# hodiny.net
KiCad netlist of a schematic drawn in EAGLE
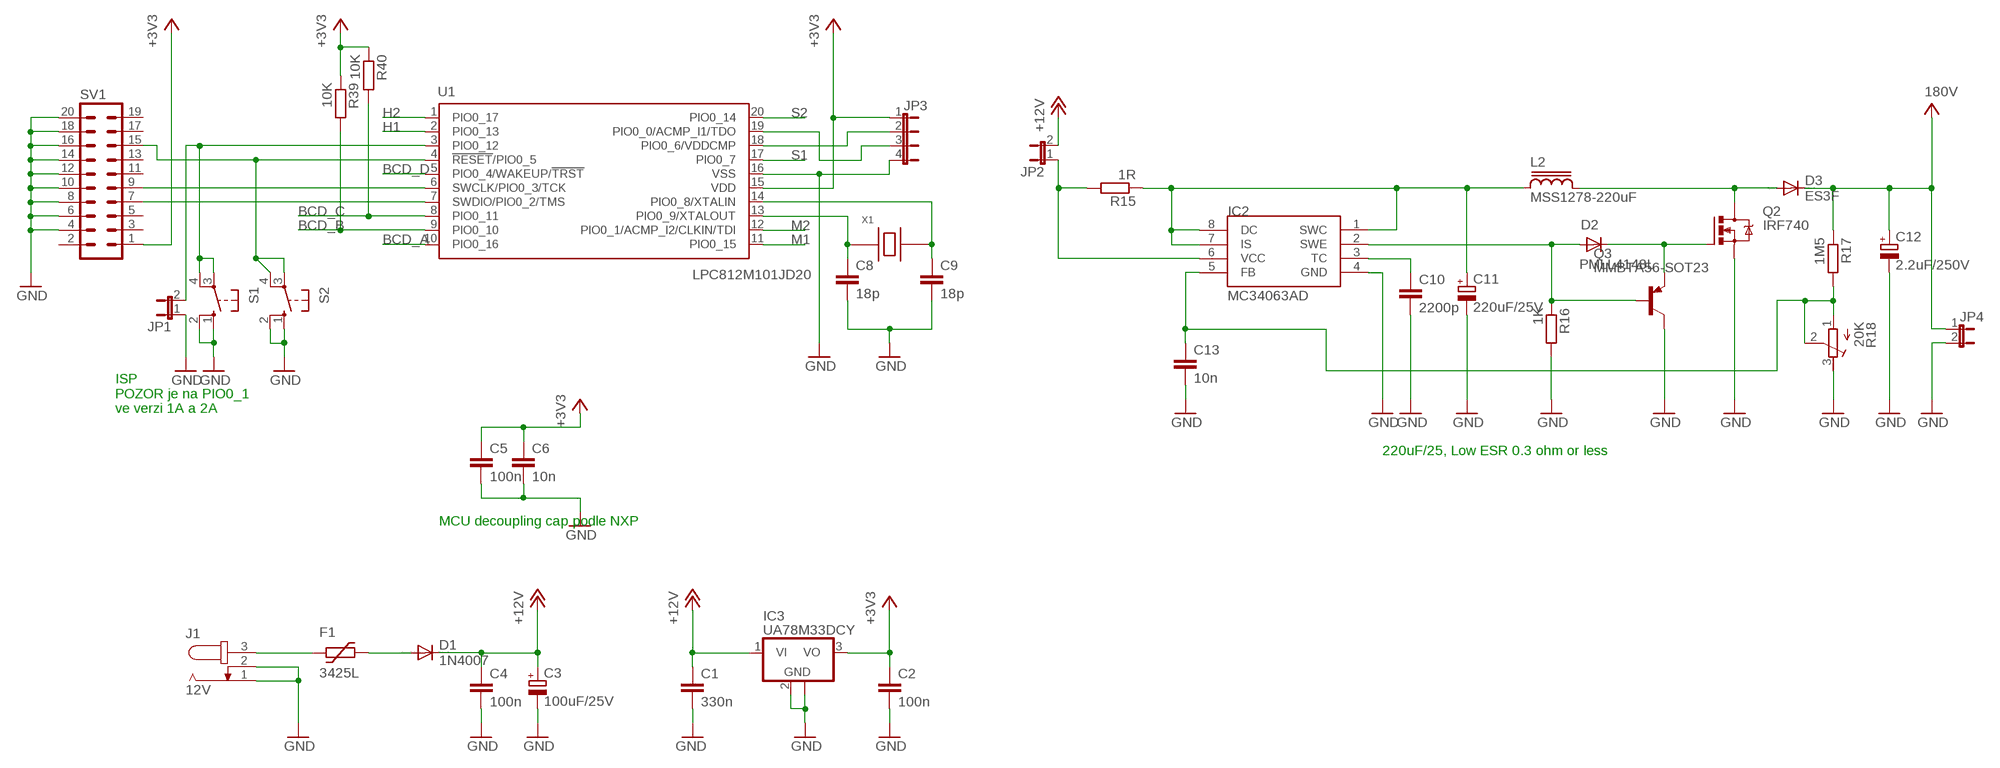
[diagram p0: schematic, sheet 1]
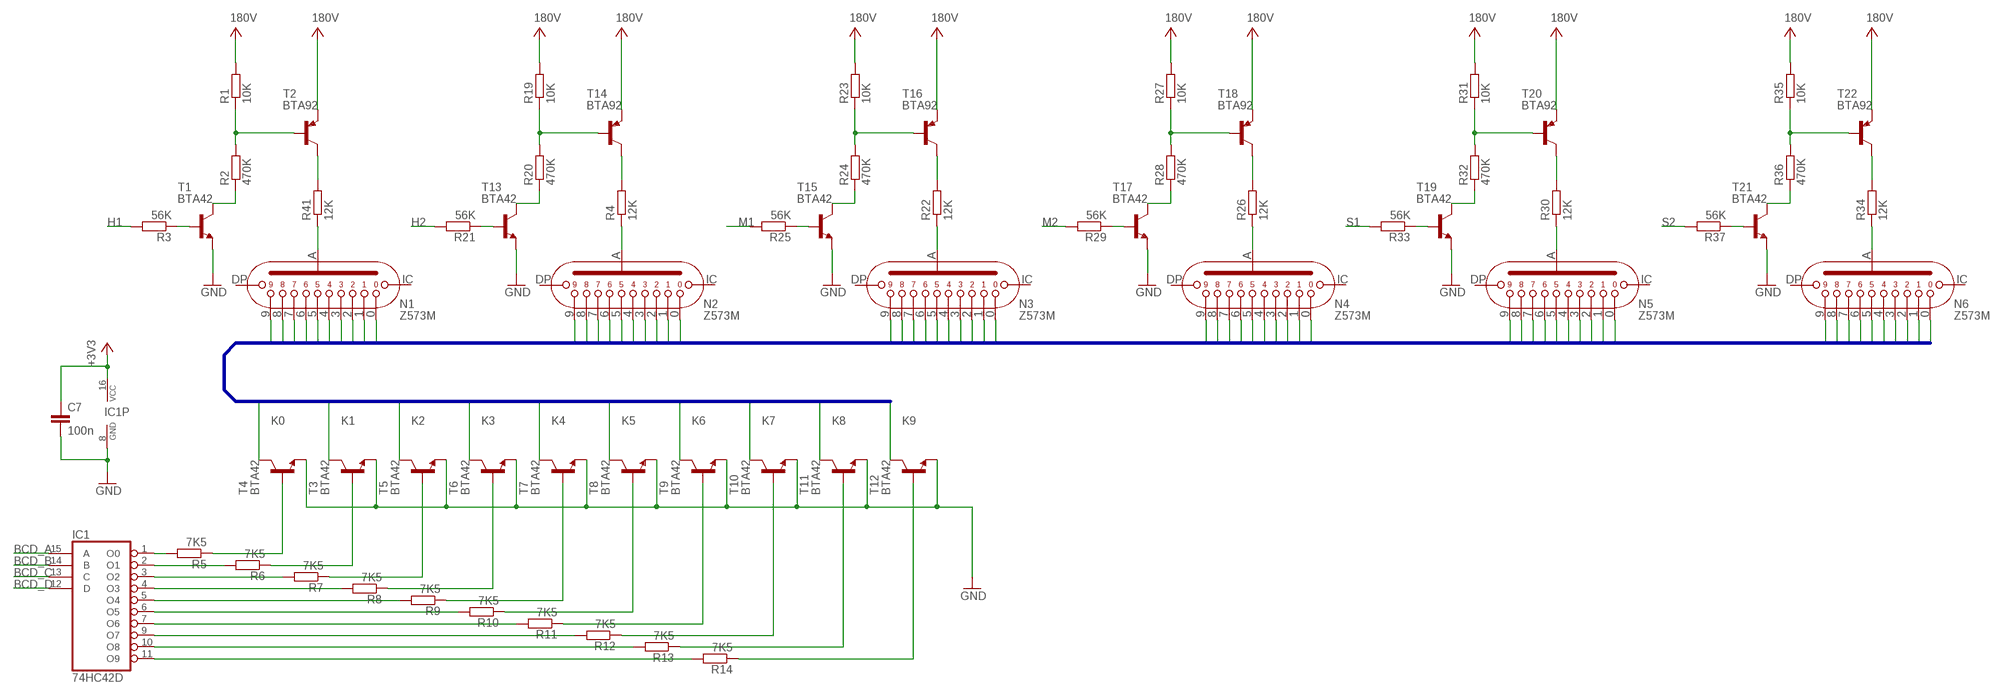
[diagram p1: schematic, sheet 2]

(export (version "E")
  (design (tool "Eeschema 10.0.6"))
  (components
    (comp (ref "C1")
      (value "330n")
      (footprint "eagle-import:C1206")
      (libsource (lib "eagle-import") (part "C-EUC1206"))
    )
    (comp (ref "C2")
      (value "100n")
      (footprint "eagle-import:C1206")
      (libsource (lib "eagle-import") (part "C-EUC1206"))
    )
    (comp (ref "C3")
      (value "100uF/25V")
      (footprint "eagle-import:153CLV-0605")
      (libsource (lib "eagle-import") (part "CPOL-EU153CLV-0605"))
    )
    (comp (ref "C4")
      (value "100n")
      (footprint "eagle-import:C1206")
      (libsource (lib "eagle-import") (part "C-EUC1206"))
    )
    (comp (ref "C5")
      (value "100n")
      (footprint "eagle-import:C1206")
      (libsource (lib "eagle-import") (part "C-EUC1206"))
    )
    (comp (ref "C6")
      (value "10n")
      (footprint "eagle-import:C1206")
      (libsource (lib "eagle-import") (part "C-EUC1206"))
    )
    (comp (ref "C8")
      (value "18p")
      (footprint "eagle-import:C0805")
      (libsource (lib "eagle-import") (part "C-EUC0805"))
    )
    (comp (ref "C9")
      (value "18p")
      (footprint "eagle-import:C0805")
      (libsource (lib "eagle-import") (part "C-EUC0805"))
    )
    (comp (ref "C10")
      (value "2200p")
      (footprint "eagle-import:C1206")
      (libsource (lib "eagle-import") (part "C-EUC1206"))
    )
    (comp (ref "C11")
      (value "220uF/25V")
      (footprint "eagle-import:153CLV-0605")
      (libsource (lib "eagle-import") (part "CPOL-EU153CLV-0605"))
    )
    (comp (ref "C12")
      (value "2.2uF/250V")
      (footprint "eagle-import:E2,5-6")
      (libsource (lib "eagle-import") (part "CPOL-EUE2.5-6"))
    )
    (comp (ref "C13")
      (value "10n")
      (footprint "eagle-import:C1206")
      (libsource (lib "eagle-import") (part "C-EUC1206"))
    )
    (comp (ref "D1")
      (value "1N4007")
      (footprint "eagle-import:MELF-MLL41")
      (libsource (lib "eagle-import") (part "DIODE-MELF-MLL41"))
    )
    (comp (ref "D2")
      (value "PMLL4148L")
      (footprint "eagle-import:SOD80C")
      (libsource (lib "eagle-import") (part "PMLL4148L"))
    )
    (comp (ref "D3")
      (value "ES3F")
      (footprint "eagle-import:SMC")
      (libsource (lib "eagle-import") (part "DIODE-SMC"))
    )
    (comp (ref "F1")
      (value "3425L")
      (footprint "eagle-import:3425L")
      (libsource (lib "eagle-import") (part "3425L"))
    )
    (comp (ref "IC2")
      (value "MC34063AD")
      (footprint "eagle-import:SOIC8")
      (libsource (lib "eagle-import") (part "MC34063AD"))
    )
    (comp (ref "IC3")
      (value "UA78M33DCY")
      (footprint "eagle-import:SOT223")
      (libsource (lib "eagle-import") (part "UA78MDCY33"))
    )
    (comp (ref "J1")
      (value "12V")
      (footprint "eagle-import:SPC4077")
      (libsource (lib "eagle-import") (part "JACK-PLUG0"))
    )
    (comp (ref "JP1")
      (value "JP1E")
      (footprint "eagle-import:JP1")
      (libsource (lib "eagle-import") (part "JP1E"))
    )
    (comp (ref "JP2")
      (value "JP1E")
      (footprint "eagle-import:JP1")
      (libsource (lib "eagle-import") (part "JP1E"))
    )
    (comp (ref "JP3")
      (value "JP4E")
      (footprint "eagle-import:JP4")
      (libsource (lib "eagle-import") (part "JP4E"))
    )
    (comp (ref "JP4")
      (value "JP1E")
      (footprint "eagle-import:JP1")
      (libsource (lib "eagle-import") (part "JP1E"))
    )
    (comp (ref "L2")
      (value "MSS1278-220uF")
      (footprint "eagle-import:MSS1278")
      (libsource (lib "eagle-import") (part "MSS1278"))
    )
    (comp (ref "Q2")
      (value "IRF740")
      (footprint "eagle-import:TO220BV")
      (libsource (lib "eagle-import") (part "IRF740"))
    )
    (comp (ref "Q3")
      (value "MMBTA56-SOT23")
      (footprint "eagle-import:SOT23")
      (libsource (lib "eagle-import") (part "-?SOT23MMBTA56"))
    )
    (comp (ref "R15")
      (value "1R")
      (footprint "eagle-import:R1206")
      (libsource (lib "eagle-import") (part "R-EU_R1206"))
    )
    (comp (ref "R16")
      (value "1K")
      (footprint "eagle-import:R1206")
      (libsource (lib "eagle-import") (part "R-EU_R1206"))
    )
    (comp (ref "R17")
      (value "1M5")
      (footprint "eagle-import:R1206")
      (libsource (lib "eagle-import") (part "R-EU_R1206"))
    )
    (comp (ref "R18")
      (value "20K")
      (footprint "eagle-import:RTRIMTSM53YJ")
      (libsource (lib "eagle-import") (part "R-TRIMMTSM53YJ"))
    )
    (comp (ref "R39")
      (value "10K")
      (footprint "eagle-import:R1206")
      (libsource (lib "eagle-import") (part "R-EU_R1206"))
    )
    (comp (ref "R40")
      (value "10K")
      (footprint "eagle-import:R1206")
      (libsource (lib "eagle-import") (part "R-EU_R1206"))
    )
    (comp (ref "S1")
      (value "10-XX")
      (footprint "eagle-import:B3F-10XX")
      (fields (field (name "MPN") "B3F-1000"))
      (libsource (lib "eagle-import") (part "10-XX"))
    )
    (comp (ref "S2")
      (value "10-XX")
      (footprint "eagle-import:B3F-10XX")
      (fields (field (name "MPN") "B3F-1000"))
      (libsource (lib "eagle-import") (part "10-XX"))
    )
    (comp (ref "SV1")
      (value "ML20")
      (footprint "eagle-import:ML20")
      (libsource (lib "eagle-import") (part "ML20"))
    )
    (comp (ref "U1")
      (value "LPC812M101JD20")
      (footprint "eagle-import:SOT163-1")
      (libsource (lib "eagle-import") (part "LPC812M101JD20"))
    )
    (comp (ref "X1")
      (value "SMCE-5032")
      (footprint "eagle-import:IQG5032B")
      (libsource (lib "eagle-import") (part "SMCE-5032"))
    )
    (comp (ref "C7")
      (value "100n")
      (footprint "eagle-import:C1206")
      (libsource (lib "eagle-import") (part "C-EUC1206"))
    )
    (comp (ref "IC1")
      (value "74HC42D")
      (footprint "eagle-import:SO16")
      (libsource (lib "eagle-import") (part "7442DHC"))
    )
    (comp (ref "N1")
      (value "Z573M")
      (footprint "eagle-import:Z570M")
      (libsource (lib "eagle-import") (part "Z573M"))
    )
    (comp (ref "N2")
      (value "Z573M")
      (footprint "eagle-import:Z570M")
      (libsource (lib "eagle-import") (part "Z573M"))
    )
    (comp (ref "N3")
      (value "Z573M")
      (footprint "eagle-import:Z570M")
      (libsource (lib "eagle-import") (part "Z573M"))
    )
    (comp (ref "N4")
      (value "Z573M")
      (footprint "eagle-import:Z570M")
      (libsource (lib "eagle-import") (part "Z573M"))
    )
    (comp (ref "N5")
      (value "Z573M")
      (footprint "eagle-import:Z570M")
      (libsource (lib "eagle-import") (part "Z573M"))
    )
    (comp (ref "N6")
      (value "Z573M")
      (footprint "eagle-import:Z570M")
      (libsource (lib "eagle-import") (part "Z573M"))
    )
    (comp (ref "R1")
      (value "10K")
      (footprint "eagle-import:R1206")
      (libsource (lib "eagle-import") (part "R-EU_R1206"))
    )
    (comp (ref "R2")
      (value "470K")
      (footprint "eagle-import:R1206")
      (libsource (lib "eagle-import") (part "R-EU_R1206"))
    )
    (comp (ref "R3")
      (value "56K")
      (footprint "eagle-import:R1206")
      (libsource (lib "eagle-import") (part "R-EU_R1206"))
    )
    (comp (ref "R4")
      (value "12K")
      (footprint "eagle-import:0207_7")
      (libsource (lib "eagle-import") (part "R-EU_0207/7"))
    )
    (comp (ref "R5")
      (value "7K5")
      (footprint "eagle-import:R1206")
      (libsource (lib "eagle-import") (part "R-EU_R1206"))
    )
    (comp (ref "R6")
      (value "7K5")
      (footprint "eagle-import:R1206")
      (libsource (lib "eagle-import") (part "R-EU_R1206"))
    )
    (comp (ref "R7")
      (value "7K5")
      (footprint "eagle-import:R1206")
      (libsource (lib "eagle-import") (part "R-EU_R1206"))
    )
    (comp (ref "R8")
      (value "7K5")
      (footprint "eagle-import:R1206")
      (libsource (lib "eagle-import") (part "R-EU_R1206"))
    )
    (comp (ref "R9")
      (value "7K5")
      (footprint "eagle-import:R1206")
      (libsource (lib "eagle-import") (part "R-EU_R1206"))
    )
    (comp (ref "R10")
      (value "7K5")
      (footprint "eagle-import:R1206")
      (libsource (lib "eagle-import") (part "R-EU_R1206"))
    )
    (comp (ref "R11")
      (value "7K5")
      (footprint "eagle-import:R1206")
      (libsource (lib "eagle-import") (part "R-EU_R1206"))
    )
    (comp (ref "R12")
      (value "7K5")
      (footprint "eagle-import:R1206")
      (libsource (lib "eagle-import") (part "R-EU_R1206"))
    )
    (comp (ref "R13")
      (value "7K5")
      (footprint "eagle-import:R1206")
      (libsource (lib "eagle-import") (part "R-EU_R1206"))
    )
    (comp (ref "R14")
      (value "7K5")
      (footprint "eagle-import:R1206")
      (libsource (lib "eagle-import") (part "R-EU_R1206"))
    )
    (comp (ref "R19")
      (value "10K")
      (footprint "eagle-import:R1206")
      (libsource (lib "eagle-import") (part "R-EU_R1206"))
    )
    (comp (ref "R20")
      (value "470K")
      (footprint "eagle-import:R1206")
      (libsource (lib "eagle-import") (part "R-EU_R1206"))
    )
    (comp (ref "R21")
      (value "56K")
      (footprint "eagle-import:R1206")
      (libsource (lib "eagle-import") (part "R-EU_R1206"))
    )
    (comp (ref "R22")
      (value "12K")
      (footprint "eagle-import:0207_7")
      (libsource (lib "eagle-import") (part "R-EU_0207/7"))
    )
    (comp (ref "R23")
      (value "10K")
      (footprint "eagle-import:R1206")
      (libsource (lib "eagle-import") (part "R-EU_R1206"))
    )
    (comp (ref "R24")
      (value "470K")
      (footprint "eagle-import:R1206")
      (libsource (lib "eagle-import") (part "R-EU_R1206"))
    )
    (comp (ref "R25")
      (value "56K")
      (footprint "eagle-import:R1206")
      (libsource (lib "eagle-import") (part "R-EU_R1206"))
    )
    (comp (ref "R26")
      (value "12K")
      (footprint "eagle-import:0207_7")
      (libsource (lib "eagle-import") (part "R-EU_0207/7"))
    )
    (comp (ref "R27")
      (value "10K")
      (footprint "eagle-import:R1206")
      (libsource (lib "eagle-import") (part "R-EU_R1206"))
    )
    (comp (ref "R28")
      (value "470K")
      (footprint "eagle-import:R1206")
      (libsource (lib "eagle-import") (part "R-EU_R1206"))
    )
    (comp (ref "R29")
      (value "56K")
      (footprint "eagle-import:R1206")
      (libsource (lib "eagle-import") (part "R-EU_R1206"))
    )
    (comp (ref "R30")
      (value "12K")
      (footprint "eagle-import:0207_7")
      (libsource (lib "eagle-import") (part "R-EU_0207/7"))
    )
    (comp (ref "R31")
      (value "10K")
      (footprint "eagle-import:R1206")
      (libsource (lib "eagle-import") (part "R-EU_R1206"))
    )
    (comp (ref "R32")
      (value "470K")
      (footprint "eagle-import:R1206")
      (libsource (lib "eagle-import") (part "R-EU_R1206"))
    )
    (comp (ref "R33")
      (value "56K")
      (footprint "eagle-import:R1206")
      (libsource (lib "eagle-import") (part "R-EU_R1206"))
    )
    (comp (ref "R34")
      (value "12K")
      (footprint "eagle-import:0207_7")
      (libsource (lib "eagle-import") (part "R-EU_0207/7"))
    )
    (comp (ref "R35")
      (value "10K")
      (footprint "eagle-import:R1206")
      (libsource (lib "eagle-import") (part "R-EU_R1206"))
    )
    (comp (ref "R36")
      (value "470K")
      (footprint "eagle-import:R1206")
      (libsource (lib "eagle-import") (part "R-EU_R1206"))
    )
    (comp (ref "R37")
      (value "56K")
      (footprint "eagle-import:R1206")
      (libsource (lib "eagle-import") (part "R-EU_R1206"))
    )
    (comp (ref "R41")
      (value "12K")
      (footprint "eagle-import:0207_7")
      (libsource (lib "eagle-import") (part "R-EU_0207/7"))
    )
    (comp (ref "T1")
      (value "BTA42")
      (footprint "eagle-import:SOT23-BEC")
      (libsource (lib "eagle-import") (part "-NPN-SOT23-BECMMBTA42LT1"))
    )
    (comp (ref "T2")
      (value "BTA92")
      (footprint "eagle-import:SOT23-BEC")
      (libsource (lib "eagle-import") (part "-PNP-SOT23-BECMMBTA92LT1"))
    )
    (comp (ref "T3")
      (value "BTA42")
      (footprint "eagle-import:SOT23-BEC")
      (libsource (lib "eagle-import") (part "-NPN-SOT23-BECMMBTA42LT1"))
    )
    (comp (ref "T4")
      (value "BTA42")
      (footprint "eagle-import:SOT23-BEC")
      (libsource (lib "eagle-import") (part "-NPN-SOT23-BECMMBTA42LT1"))
    )
    (comp (ref "T5")
      (value "BTA42")
      (footprint "eagle-import:SOT23-BEC")
      (libsource (lib "eagle-import") (part "-NPN-SOT23-BECMMBTA42LT1"))
    )
    (comp (ref "T6")
      (value "BTA42")
      (footprint "eagle-import:SOT23-BEC")
      (libsource (lib "eagle-import") (part "-NPN-SOT23-BECMMBTA42LT1"))
    )
    (comp (ref "T7")
      (value "BTA42")
      (footprint "eagle-import:SOT23-BEC")
      (libsource (lib "eagle-import") (part "-NPN-SOT23-BECMMBTA42LT1"))
    )
    (comp (ref "T8")
      (value "BTA42")
      (footprint "eagle-import:SOT23-BEC")
      (libsource (lib "eagle-import") (part "-NPN-SOT23-BECMMBTA42LT1"))
    )
    (comp (ref "T9")
      (value "BTA42")
      (footprint "eagle-import:SOT23-BEC")
      (libsource (lib "eagle-import") (part "-NPN-SOT23-BECMMBTA42LT1"))
    )
    (comp (ref "T10")
      (value "BTA42")
      (footprint "eagle-import:SOT23-BEC")
      (libsource (lib "eagle-import") (part "-NPN-SOT23-BECMMBTA42LT1"))
    )
    (comp (ref "T11")
      (value "BTA42")
      (footprint "eagle-import:SOT23-BEC")
      (libsource (lib "eagle-import") (part "-NPN-SOT23-BECMMBTA42LT1"))
    )
    (comp (ref "T12")
      (value "BTA42")
      (footprint "eagle-import:SOT23-BEC")
      (libsource (lib "eagle-import") (part "-NPN-SOT23-BECMMBTA42LT1"))
    )
    (comp (ref "T13")
      (value "BTA42")
      (footprint "eagle-import:SOT23-BEC")
      (libsource (lib "eagle-import") (part "-NPN-SOT23-BECMMBTA42LT1"))
    )
    (comp (ref "T14")
      (value "BTA92")
      (footprint "eagle-import:SOT23-BEC")
      (libsource (lib "eagle-import") (part "-PNP-SOT23-BECMMBTA92LT1"))
    )
    (comp (ref "T15")
      (value "BTA42")
      (footprint "eagle-import:SOT23-BEC")
      (libsource (lib "eagle-import") (part "-NPN-SOT23-BECMMBTA42LT1"))
    )
    (comp (ref "T16")
      (value "BTA92")
      (footprint "eagle-import:SOT23-BEC")
      (libsource (lib "eagle-import") (part "-PNP-SOT23-BECMMBTA92LT1"))
    )
    (comp (ref "T17")
      (value "BTA42")
      (footprint "eagle-import:SOT23-BEC")
      (libsource (lib "eagle-import") (part "-NPN-SOT23-BECMMBTA42LT1"))
    )
    (comp (ref "T18")
      (value "BTA92")
      (footprint "eagle-import:SOT23-BEC")
      (libsource (lib "eagle-import") (part "-PNP-SOT23-BECMMBTA92LT1"))
    )
    (comp (ref "T19")
      (value "BTA42")
      (footprint "eagle-import:SOT23-BEC")
      (libsource (lib "eagle-import") (part "-NPN-SOT23-BECMMBTA42LT1"))
    )
    (comp (ref "T20")
      (value "BTA92")
      (footprint "eagle-import:SOT23-BEC")
      (libsource (lib "eagle-import") (part "-PNP-SOT23-BECMMBTA92LT1"))
    )
    (comp (ref "T21")
      (value "BTA42")
      (footprint "eagle-import:SOT23-BEC")
      (libsource (lib "eagle-import") (part "-NPN-SOT23-BECMMBTA42LT1"))
    )
    (comp (ref "T22")
      (value "BTA92")
      (footprint "eagle-import:SOT23-BEC")
      (libsource (lib "eagle-import") (part "-PNP-SOT23-BECMMBTA92LT1"))
    )
  )
  (nets
    (net (code "1") (name "+3V3") (class "Default")
      (node (ref "C2") (pin "1") (pinfunction "1_1") (pintype "passive"))
      (node (ref "C5") (pin "1") (pinfunction "1_1") (pintype "passive"))
      (node (ref "C6") (pin "1") (pinfunction "1_1") (pintype "passive"))
      (node (ref "C7") (pin "1") (pinfunction "1_1") (pintype "passive"))
      (node (ref "IC1") (pin "16") (pinfunction "VCC_16") (pintype "power_in"))
      (node (ref "IC3") (pin "3") (pinfunction "VO_3") (pintype "passive"))
      (node (ref "JP3") (pin "1") (pinfunction "1_1") (pintype "passive"))
      (node (ref "R39") (pin "1") (pinfunction "1_1") (pintype "passive"))
      (node (ref "R40") (pin "1") (pinfunction "1_1") (pintype "passive"))
      (node (ref "SV1") (pin "1") (pinfunction "1_1") (pintype "passive"))
      (node (ref "U1") (pin "15") (pinfunction "VDD_15") (pintype "power_in"))
    )
    (net (code "2") (name "+12V") (class "Default")
      (node (ref "C1") (pin "1") (pinfunction "1_1") (pintype "passive"))
      (node (ref "C3") (pin "+") (pinfunction "+_+") (pintype "passive"))
      (node (ref "C4") (pin "1") (pinfunction "1_1") (pintype "passive"))
      (node (ref "D1") (pin "C") (pinfunction "C_C") (pintype "passive"))
      (node (ref "IC3") (pin "1") (pinfunction "VI_1") (pintype "input"))
      (node (ref "JP2") (pin "2") (pinfunction "2_2") (pintype "passive"))
    )
    (net (code "3") (name "BCD_A") (class "Default")
      (node (ref "IC1") (pin "15") (pinfunction "A_15") (pintype "input"))
      (node (ref "U1") (pin "10") (pinfunction "PIO0_16_10") (pintype "bidirectional"))
    )
    (net (code "4") (name "BCD_B") (class "Default")
      (node (ref "IC1") (pin "14") (pinfunction "B_14") (pintype "input"))
      (node (ref "R39") (pin "2") (pinfunction "2_2") (pintype "passive"))
      (node (ref "U1") (pin "9") (pinfunction "PIO0_10_9") (pintype "bidirectional"))
    )
    (net (code "5") (name "BCD_C") (class "Default")
      (node (ref "IC1") (pin "13") (pinfunction "C_13") (pintype "input"))
      (node (ref "R40") (pin "2") (pinfunction "2_2") (pintype "passive"))
      (node (ref "U1") (pin "8") (pinfunction "PIO0_11_8") (pintype "bidirectional"))
    )
    (net (code "6") (name "BCD_D") (class "Default")
      (node (ref "IC1") (pin "12") (pinfunction "D_12") (pintype "input"))
      (node (ref "U1") (pin "5") (pinfunction "PIO0_4/WAKEUP/~{TRST}_5") (pintype "bidirectional"))
    )
    (net (code "7") (name "GND") (class "Default")
      (node (ref "C1") (pin "2") (pinfunction "2_2") (pintype "passive"))
      (node (ref "C10") (pin "2") (pinfunction "2_2") (pintype "passive"))
      (node (ref "C11") (pin "-") (pinfunction "-_-") (pintype "passive"))
      (node (ref "C12") (pin "-") (pinfunction "-_-") (pintype "passive"))
      (node (ref "C13") (pin "2") (pinfunction "2_2") (pintype "passive"))
      (node (ref "C2") (pin "2") (pinfunction "2_2") (pintype "passive"))
      (node (ref "C3") (pin "-") (pinfunction "-_-") (pintype "passive"))
      (node (ref "C4") (pin "2") (pinfunction "2_2") (pintype "passive"))
      (node (ref "C5") (pin "2") (pinfunction "2_2") (pintype "passive"))
      (node (ref "C6") (pin "2") (pinfunction "2_2") (pintype "passive"))
      (node (ref "C7") (pin "2") (pinfunction "2_2") (pintype "passive"))
      (node (ref "C8") (pin "2") (pinfunction "2_2") (pintype "passive"))
      (node (ref "C9") (pin "2") (pinfunction "2_2") (pintype "passive"))
      (node (ref "IC1") (pin "8") (pinfunction "GND_8") (pintype "power_in"))
      (node (ref "IC2") (pin "4") (pinfunction "GND_4") (pintype "passive"))
      (node (ref "IC3") (pin "2") (pinfunction "GND_2") (pintype "passive"))
      (node (ref "IC3") (pin "4") (pinfunction "GND_4") (pintype "passive"))
      (node (ref "J1") (pin "1") (pinfunction "1_1") (pintype "passive"))
      (node (ref "J1") (pin "2") (pinfunction "2_2") (pintype "passive"))
      (node (ref "JP1") (pin "1") (pinfunction "1_1") (pintype "passive"))
      (node (ref "JP3") (pin "4") (pinfunction "4_4") (pintype "passive"))
      (node (ref "JP4") (pin "2") (pinfunction "2_2") (pintype "passive"))
      (node (ref "Q2") (pin "S") (pinfunction "S_S") (pintype "passive"))
      (node (ref "Q3") (pin "3") (pinfunction "C_3") (pintype "passive"))
      (node (ref "R16") (pin "2") (pinfunction "2_2") (pintype "passive"))
      (node (ref "R18") (pin "3") (pinfunction "E_3") (pintype "passive"))
      (node (ref "S1") (pin "1") (pinfunction "S_1") (pintype "passive"))
      (node (ref "S1") (pin "2") (pinfunction "S1_2") (pintype "passive"))
      (node (ref "S2") (pin "1") (pinfunction "S_1") (pintype "passive"))
      (node (ref "S2") (pin "2") (pinfunction "S1_2") (pintype "passive"))
      (node (ref "SV1") (pin "10") (pinfunction "10_10") (pintype "passive"))
      (node (ref "SV1") (pin "12") (pinfunction "12_12") (pintype "passive"))
      (node (ref "SV1") (pin "14") (pinfunction "14_14") (pintype "passive"))
      (node (ref "SV1") (pin "16") (pinfunction "16_16") (pintype "passive"))
      (node (ref "SV1") (pin "18") (pinfunction "18_18") (pintype "passive"))
      (node (ref "SV1") (pin "20") (pinfunction "20_20") (pintype "passive"))
      (node (ref "SV1") (pin "4") (pinfunction "4_4") (pintype "passive"))
      (node (ref "SV1") (pin "6") (pinfunction "6_6") (pintype "passive"))
      (node (ref "SV1") (pin "8") (pinfunction "8_8") (pintype "passive"))
      (node (ref "T1") (pin "E") (pinfunction "E_E") (pintype "passive"))
      (node (ref "T10") (pin "E") (pinfunction "E_E") (pintype "passive"))
      (node (ref "T11") (pin "E") (pinfunction "E_E") (pintype "passive"))
      (node (ref "T12") (pin "E") (pinfunction "E_E") (pintype "passive"))
      (node (ref "T13") (pin "E") (pinfunction "E_E") (pintype "passive"))
      (node (ref "T15") (pin "E") (pinfunction "E_E") (pintype "passive"))
      (node (ref "T17") (pin "E") (pinfunction "E_E") (pintype "passive"))
      (node (ref "T19") (pin "E") (pinfunction "E_E") (pintype "passive"))
      (node (ref "T21") (pin "E") (pinfunction "E_E") (pintype "passive"))
      (node (ref "T3") (pin "E") (pinfunction "E_E") (pintype "passive"))
      (node (ref "T4") (pin "E") (pinfunction "E_E") (pintype "passive"))
      (node (ref "T5") (pin "E") (pinfunction "E_E") (pintype "passive"))
      (node (ref "T6") (pin "E") (pinfunction "E_E") (pintype "passive"))
      (node (ref "T7") (pin "E") (pinfunction "E_E") (pintype "passive"))
      (node (ref "T8") (pin "E") (pinfunction "E_E") (pintype "passive"))
      (node (ref "T9") (pin "E") (pinfunction "E_E") (pintype "passive"))
      (node (ref "U1") (pin "16") (pinfunction "VSS_16") (pintype "power_in"))
    )
    (net (code "8") (name "H1") (class "Default")
      (node (ref "R3") (pin "2") (pinfunction "2_2") (pintype "passive"))
      (node (ref "U1") (pin "2") (pinfunction "PIO0_13_2") (pintype "bidirectional"))
    )
    (net (code "9") (name "H2") (class "Default")
      (node (ref "R21") (pin "2") (pinfunction "2_2") (pintype "passive"))
      (node (ref "U1") (pin "1") (pinfunction "PIO0_17_1") (pintype "bidirectional"))
    )
    (net (code "10") (name "K0") (class "Default")
      (node (ref "N1") (pin "12") (pinfunction "0_12") (pintype "bidirectional"))
      (node (ref "N2") (pin "12") (pinfunction "0_12") (pintype "bidirectional"))
      (node (ref "N3") (pin "12") (pinfunction "0_12") (pintype "bidirectional"))
      (node (ref "N4") (pin "12") (pinfunction "0_12") (pintype "bidirectional"))
      (node (ref "N5") (pin "12") (pinfunction "0_12") (pintype "bidirectional"))
      (node (ref "N6") (pin "12") (pinfunction "0_12") (pintype "bidirectional"))
      (node (ref "T4") (pin "C") (pinfunction "C_C") (pintype "passive"))
    )
    (net (code "11") (name "K1") (class "Default")
      (node (ref "N1") (pin "1") (pinfunction "1_1") (pintype "bidirectional"))
      (node (ref "N2") (pin "1") (pinfunction "1_1") (pintype "bidirectional"))
      (node (ref "N3") (pin "1") (pinfunction "1_1") (pintype "bidirectional"))
      (node (ref "N4") (pin "1") (pinfunction "1_1") (pintype "bidirectional"))
      (node (ref "N5") (pin "1") (pinfunction "1_1") (pintype "bidirectional"))
      (node (ref "N6") (pin "1") (pinfunction "1_1") (pintype "bidirectional"))
      (node (ref "T3") (pin "C") (pinfunction "C_C") (pintype "passive"))
    )
    (net (code "12") (name "K2") (class "Default")
      (node (ref "N1") (pin "2") (pinfunction "2_2") (pintype "bidirectional"))
      (node (ref "N2") (pin "2") (pinfunction "2_2") (pintype "bidirectional"))
      (node (ref "N3") (pin "2") (pinfunction "2_2") (pintype "bidirectional"))
      (node (ref "N4") (pin "2") (pinfunction "2_2") (pintype "bidirectional"))
      (node (ref "N5") (pin "2") (pinfunction "2_2") (pintype "bidirectional"))
      (node (ref "N6") (pin "2") (pinfunction "2_2") (pintype "bidirectional"))
      (node (ref "T5") (pin "C") (pinfunction "C_C") (pintype "passive"))
    )
    (net (code "13") (name "K3") (class "Default")
      (node (ref "N1") (pin "3") (pinfunction "3_3") (pintype "bidirectional"))
      (node (ref "N2") (pin "3") (pinfunction "3_3") (pintype "bidirectional"))
      (node (ref "N3") (pin "3") (pinfunction "3_3") (pintype "bidirectional"))
      (node (ref "N4") (pin "3") (pinfunction "3_3") (pintype "bidirectional"))
      (node (ref "N5") (pin "3") (pinfunction "3_3") (pintype "bidirectional"))
      (node (ref "N6") (pin "3") (pinfunction "3_3") (pintype "bidirectional"))
      (node (ref "T6") (pin "C") (pinfunction "C_C") (pintype "passive"))
    )
    (net (code "14") (name "K4") (class "Default")
      (node (ref "N1") (pin "5") (pinfunction "4_5") (pintype "bidirectional"))
      (node (ref "N2") (pin "5") (pinfunction "4_5") (pintype "bidirectional"))
      (node (ref "N3") (pin "5") (pinfunction "4_5") (pintype "bidirectional"))
      (node (ref "N4") (pin "5") (pinfunction "4_5") (pintype "bidirectional"))
      (node (ref "N5") (pin "5") (pinfunction "4_5") (pintype "bidirectional"))
      (node (ref "N6") (pin "5") (pinfunction "4_5") (pintype "bidirectional"))
      (node (ref "T7") (pin "C") (pinfunction "C_C") (pintype "passive"))
    )
    (net (code "15") (name "K5") (class "Default")
      (node (ref "N1") (pin "6") (pinfunction "5_6") (pintype "bidirectional"))
      (node (ref "N2") (pin "6") (pinfunction "5_6") (pintype "bidirectional"))
      (node (ref "N3") (pin "6") (pinfunction "5_6") (pintype "bidirectional"))
      (node (ref "N4") (pin "6") (pinfunction "5_6") (pintype "bidirectional"))
      (node (ref "N5") (pin "6") (pinfunction "5_6") (pintype "bidirectional"))
      (node (ref "N6") (pin "6") (pinfunction "5_6") (pintype "bidirectional"))
      (node (ref "T8") (pin "C") (pinfunction "C_C") (pintype "passive"))
    )
    (net (code "16") (name "K6") (class "Default")
      (node (ref "N1") (pin "7") (pinfunction "6_7") (pintype "bidirectional"))
      (node (ref "N2") (pin "7") (pinfunction "6_7") (pintype "bidirectional"))
      (node (ref "N3") (pin "7") (pinfunction "6_7") (pintype "bidirectional"))
      (node (ref "N4") (pin "7") (pinfunction "6_7") (pintype "bidirectional"))
      (node (ref "N5") (pin "7") (pinfunction "6_7") (pintype "bidirectional"))
      (node (ref "N6") (pin "7") (pinfunction "6_7") (pintype "bidirectional"))
      (node (ref "T9") (pin "C") (pinfunction "C_C") (pintype "passive"))
    )
    (net (code "17") (name "K7") (class "Default")
      (node (ref "N1") (pin "8") (pinfunction "7_8") (pintype "bidirectional"))
      (node (ref "N2") (pin "8") (pinfunction "7_8") (pintype "bidirectional"))
      (node (ref "N3") (pin "8") (pinfunction "7_8") (pintype "bidirectional"))
      (node (ref "N4") (pin "8") (pinfunction "7_8") (pintype "bidirectional"))
      (node (ref "N5") (pin "8") (pinfunction "7_8") (pintype "bidirectional"))
      (node (ref "N6") (pin "8") (pinfunction "7_8") (pintype "bidirectional"))
      (node (ref "T10") (pin "C") (pinfunction "C_C") (pintype "passive"))
    )
    (net (code "18") (name "K8") (class "Default")
      (node (ref "N1") (pin "9") (pinfunction "8_9") (pintype "bidirectional"))
      (node (ref "N2") (pin "9") (pinfunction "8_9") (pintype "bidirectional"))
      (node (ref "N3") (pin "9") (pinfunction "8_9") (pintype "bidirectional"))
      (node (ref "N4") (pin "9") (pinfunction "8_9") (pintype "bidirectional"))
      (node (ref "N5") (pin "9") (pinfunction "8_9") (pintype "bidirectional"))
      (node (ref "N6") (pin "9") (pinfunction "8_9") (pintype "bidirectional"))
      (node (ref "T11") (pin "C") (pinfunction "C_C") (pintype "passive"))
    )
    (net (code "19") (name "K9") (class "Default")
      (node (ref "N1") (pin "11") (pinfunction "9_11") (pintype "bidirectional"))
      (node (ref "N2") (pin "11") (pinfunction "9_11") (pintype "bidirectional"))
      (node (ref "N3") (pin "11") (pinfunction "9_11") (pintype "bidirectional"))
      (node (ref "N4") (pin "11") (pinfunction "9_11") (pintype "bidirectional"))
      (node (ref "N5") (pin "11") (pinfunction "9_11") (pintype "bidirectional"))
      (node (ref "N6") (pin "11") (pinfunction "9_11") (pintype "bidirectional"))
      (node (ref "T12") (pin "C") (pinfunction "C_C") (pintype "passive"))
    )
    (net (code "20") (name "M1") (class "Default")
      (node (ref "R25") (pin "2") (pinfunction "2_2") (pintype "passive"))
      (node (ref "U1") (pin "11") (pinfunction "PIO0_15_11") (pintype "bidirectional"))
    )
    (net (code "21") (name "M2") (class "Default")
      (node (ref "R29") (pin "2") (pinfunction "2_2") (pintype "passive"))
      (node (ref "U1") (pin "12") (pinfunction "PIO0_1/ACMP_I2/CLKIN/TDI_12") (pintype "bidirectional"))
    )
    (net (code "22") (name "Net-(D2-A)") (class "Default")
      (node (ref "D2") (pin "2") (pinfunction "A_2") (pintype "passive"))
      (node (ref "IC2") (pin "2") (pinfunction "SWE_2") (pintype "passive"))
      (node (ref "Q3") (pin "1") (pinfunction "B_1") (pintype "passive"))
      (node (ref "R16") (pin "1") (pinfunction "1_1") (pintype "passive"))
    )
    (net (code "23") (name "Net-(D2-K)") (class "Default")
      (node (ref "D2") (pin "1") (pinfunction "K_1") (pintype "passive"))
      (node (ref "Q2") (pin "G") (pinfunction "G_G") (pintype "passive"))
      (node (ref "Q3") (pin "2") (pinfunction "E_2") (pintype "passive"))
    )
    (net (code "24") (name "Net-(D3-PadA)") (class "Default")
      (node (ref "D3") (pin "A") (pinfunction "A_A") (pintype "passive"))
      (node (ref "L2") (pin "2") (pinfunction "2_2") (pintype "passive"))
      (node (ref "Q2") (pin "D") (pinfunction "D_D") (pintype "passive"))
    )
    (net (code "25") (name "Net-(F1-1)") (class "Default")
      (node (ref "F1") (pin "P$1") (pinfunction "1_P$1") (pintype "passive"))
      (node (ref "J1") (pin "3") (pinfunction "3_3") (pintype "passive"))
    )
    (net (code "26") (name "Net-(F1-2)") (class "Default")
      (node (ref "D1") (pin "A") (pinfunction "A_A") (pintype "passive"))
      (node (ref "F1") (pin "P$2") (pinfunction "2_P$2") (pintype "passive"))
    )
    (net (code "27") (name "Net-(IC1A-O0)") (class "Default")
      (node (ref "IC1") (pin "1") (pinfunction "O0_1") (pintype "output"))
      (node (ref "R5") (pin "2") (pinfunction "2_2") (pintype "passive"))
    )
    (net (code "28") (name "Net-(IC1A-O1)") (class "Default")
      (node (ref "IC1") (pin "2") (pinfunction "O1_2") (pintype "output"))
      (node (ref "R6") (pin "2") (pinfunction "2_2") (pintype "passive"))
    )
    (net (code "29") (name "Net-(IC1A-O2)") (class "Default")
      (node (ref "IC1") (pin "3") (pinfunction "O2_3") (pintype "output"))
      (node (ref "R7") (pin "2") (pinfunction "2_2") (pintype "passive"))
    )
    (net (code "30") (name "Net-(IC1A-O3)") (class "Default")
      (node (ref "IC1") (pin "4") (pinfunction "O3_4") (pintype "output"))
      (node (ref "R8") (pin "2") (pinfunction "2_2") (pintype "passive"))
    )
    (net (code "31") (name "Net-(IC1A-O4)") (class "Default")
      (node (ref "IC1") (pin "5") (pinfunction "O4_5") (pintype "output"))
      (node (ref "R9") (pin "2") (pinfunction "2_2") (pintype "passive"))
    )
    (net (code "32") (name "Net-(IC1A-O5)") (class "Default")
      (node (ref "IC1") (pin "6") (pinfunction "O5_6") (pintype "output"))
      (node (ref "R10") (pin "2") (pinfunction "2_2") (pintype "passive"))
    )
    (net (code "33") (name "Net-(IC1A-O6)") (class "Default")
      (node (ref "IC1") (pin "7") (pinfunction "O6_7") (pintype "output"))
      (node (ref "R11") (pin "2") (pinfunction "2_2") (pintype "passive"))
    )
    (net (code "34") (name "Net-(IC1A-O7)") (class "Default")
      (node (ref "IC1") (pin "9") (pinfunction "O7_9") (pintype "output"))
      (node (ref "R12") (pin "2") (pinfunction "2_2") (pintype "passive"))
    )
    (net (code "35") (name "Net-(IC1A-O8)") (class "Default")
      (node (ref "IC1") (pin "10") (pinfunction "O8_10") (pintype "output"))
      (node (ref "R13") (pin "2") (pinfunction "2_2") (pintype "passive"))
    )
    (net (code "36") (name "Net-(IC1A-O9)") (class "Default")
      (node (ref "IC1") (pin "11") (pinfunction "O9_11") (pintype "output"))
      (node (ref "R14") (pin "2") (pinfunction "2_2") (pintype "passive"))
    )
    (net (code "37") (name "Net-(IC2-DC)") (class "Default")
      (node (ref "C11") (pin "+") (pinfunction "+_+") (pintype "passive"))
      (node (ref "IC2") (pin "1") (pinfunction "SWC_1") (pintype "passive"))
      (node (ref "IC2") (pin "7") (pinfunction "IS_7") (pintype "passive"))
      (node (ref "IC2") (pin "8") (pinfunction "DC_8") (pintype "passive"))
      (node (ref "L2") (pin "1") (pinfunction "1_1") (pintype "passive"))
      (node (ref "R15") (pin "1") (pinfunction "1_1") (pintype "passive"))
    )
    (net (code "38") (name "Net-(IC2-FB)") (class "Default")
      (node (ref "C13") (pin "1") (pinfunction "1_1") (pintype "passive"))
      (node (ref "IC2") (pin "5") (pinfunction "FB_5") (pintype "passive"))
      (node (ref "R17") (pin "2") (pinfunction "2_2") (pintype "passive"))
      (node (ref "R18") (pin "1") (pinfunction "A_1") (pintype "passive"))
      (node (ref "R18") (pin "2") (pinfunction "S_2") (pintype "passive"))
    )
    (net (code "39") (name "Net-(IC2-TC)") (class "Default")
      (node (ref "C10") (pin "1") (pinfunction "1_1") (pintype "passive"))
      (node (ref "IC2") (pin "3") (pinfunction "TC_3") (pintype "passive"))
    )
    (net (code "40") (name "Net-(IC2-VCC)") (class "Default")
      (node (ref "IC2") (pin "6") (pinfunction "VCC_6") (pintype "passive"))
      (node (ref "JP2") (pin "1") (pinfunction "1_1") (pintype "passive"))
      (node (ref "R15") (pin "2") (pinfunction "2_2") (pintype "passive"))
    )
    (net (code "41") (name "Net-(N1-A)") (class "Default")
      (node (ref "N1") (pin "13") (pinfunction "A_13") (pintype "bidirectional"))
      (node (ref "R41") (pin "1") (pinfunction "1_1") (pintype "passive"))
    )
    (net (code "42") (name "Net-(N2-A)") (class "Default")
      (node (ref "N2") (pin "13") (pinfunction "A_13") (pintype "bidirectional"))
      (node (ref "R4") (pin "1") (pinfunction "1_1") (pintype "passive"))
    )
    (net (code "43") (name "Net-(N3-A)") (class "Default")
      (node (ref "N3") (pin "13") (pinfunction "A_13") (pintype "bidirectional"))
      (node (ref "R22") (pin "1") (pinfunction "1_1") (pintype "passive"))
    )
    (net (code "44") (name "Net-(N4-A)") (class "Default")
      (node (ref "N4") (pin "13") (pinfunction "A_13") (pintype "bidirectional"))
      (node (ref "R26") (pin "1") (pinfunction "1_1") (pintype "passive"))
    )
    (net (code "45") (name "Net-(N5-A)") (class "Default")
      (node (ref "N5") (pin "13") (pinfunction "A_13") (pintype "bidirectional"))
      (node (ref "R30") (pin "1") (pinfunction "1_1") (pintype "passive"))
    )
    (net (code "46") (name "Net-(N6-A)") (class "Default")
      (node (ref "N6") (pin "13") (pinfunction "A_13") (pintype "bidirectional"))
      (node (ref "R34") (pin "1") (pinfunction "1_1") (pintype "passive"))
    )
    (net (code "47") (name "Net-(R1-Pad1)") (class "Default")
      (node (ref "R1") (pin "1") (pinfunction "1_1") (pintype "passive"))
      (node (ref "R2") (pin "2") (pinfunction "2_2") (pintype "passive"))
      (node (ref "T2") (pin "B") (pinfunction "B_B") (pintype "passive"))
    )
    (net (code "48") (name "Net-(R2-Pad1)") (class "Default")
      (node (ref "R2") (pin "1") (pinfunction "1_1") (pintype "passive"))
      (node (ref "T1") (pin "C") (pinfunction "C_C") (pintype "passive"))
    )
    (net (code "49") (name "Net-(R3-Pad1)") (class "Default")
      (node (ref "R3") (pin "1") (pinfunction "1_1") (pintype "passive"))
      (node (ref "T1") (pin "B") (pinfunction "B_B") (pintype "passive"))
    )
    (net (code "50") (name "Net-(R4-Pad2)") (class "Default")
      (node (ref "R4") (pin "2") (pinfunction "2_2") (pintype "passive"))
      (node (ref "T14") (pin "C") (pinfunction "C_C") (pintype "passive"))
    )
    (net (code "51") (name "Net-(R5-Pad1)") (class "Default")
      (node (ref "R5") (pin "1") (pinfunction "1_1") (pintype "passive"))
      (node (ref "T4") (pin "B") (pinfunction "B_B") (pintype "passive"))
    )
    (net (code "52") (name "Net-(R6-Pad1)") (class "Default")
      (node (ref "R6") (pin "1") (pinfunction "1_1") (pintype "passive"))
      (node (ref "T3") (pin "B") (pinfunction "B_B") (pintype "passive"))
    )
    (net (code "53") (name "Net-(R7-Pad1)") (class "Default")
      (node (ref "R7") (pin "1") (pinfunction "1_1") (pintype "passive"))
      (node (ref "T5") (pin "B") (pinfunction "B_B") (pintype "passive"))
    )
    (net (code "54") (name "Net-(R8-Pad1)") (class "Default")
      (node (ref "R8") (pin "1") (pinfunction "1_1") (pintype "passive"))
      (node (ref "T6") (pin "B") (pinfunction "B_B") (pintype "passive"))
    )
    (net (code "55") (name "Net-(R9-Pad1)") (class "Default")
      (node (ref "R9") (pin "1") (pinfunction "1_1") (pintype "passive"))
      (node (ref "T7") (pin "B") (pinfunction "B_B") (pintype "passive"))
    )
    (net (code "56") (name "Net-(R10-Pad1)") (class "Default")
      (node (ref "R10") (pin "1") (pinfunction "1_1") (pintype "passive"))
      (node (ref "T8") (pin "B") (pinfunction "B_B") (pintype "passive"))
    )
    (net (code "57") (name "Net-(R11-Pad1)") (class "Default")
      (node (ref "R11") (pin "1") (pinfunction "1_1") (pintype "passive"))
      (node (ref "T9") (pin "B") (pinfunction "B_B") (pintype "passive"))
    )
    (net (code "58") (name "Net-(R12-Pad1)") (class "Default")
      (node (ref "R12") (pin "1") (pinfunction "1_1") (pintype "passive"))
      (node (ref "T10") (pin "B") (pinfunction "B_B") (pintype "passive"))
    )
    (net (code "59") (name "Net-(R13-Pad1)") (class "Default")
      (node (ref "R13") (pin "1") (pinfunction "1_1") (pintype "passive"))
      (node (ref "T11") (pin "B") (pinfunction "B_B") (pintype "passive"))
    )
    (net (code "60") (name "Net-(R14-Pad1)") (class "Default")
      (node (ref "R14") (pin "1") (pinfunction "1_1") (pintype "passive"))
      (node (ref "T12") (pin "B") (pinfunction "B_B") (pintype "passive"))
    )
    (net (code "61") (name "Net-(R19-Pad1)") (class "Default")
      (node (ref "R19") (pin "1") (pinfunction "1_1") (pintype "passive"))
      (node (ref "R20") (pin "2") (pinfunction "2_2") (pintype "passive"))
      (node (ref "T14") (pin "B") (pinfunction "B_B") (pintype "passive"))
    )
    (net (code "62") (name "Net-(R20-Pad1)") (class "Default")
      (node (ref "R20") (pin "1") (pinfunction "1_1") (pintype "passive"))
      (node (ref "T13") (pin "C") (pinfunction "C_C") (pintype "passive"))
    )
    (net (code "63") (name "Net-(R21-Pad1)") (class "Default")
      (node (ref "R21") (pin "1") (pinfunction "1_1") (pintype "passive"))
      (node (ref "T13") (pin "B") (pinfunction "B_B") (pintype "passive"))
    )
    (net (code "64") (name "Net-(R22-Pad2)") (class "Default")
      (node (ref "R22") (pin "2") (pinfunction "2_2") (pintype "passive"))
      (node (ref "T16") (pin "C") (pinfunction "C_C") (pintype "passive"))
    )
    (net (code "65") (name "Net-(R23-Pad1)") (class "Default")
      (node (ref "R23") (pin "1") (pinfunction "1_1") (pintype "passive"))
      (node (ref "R24") (pin "2") (pinfunction "2_2") (pintype "passive"))
      (node (ref "T16") (pin "B") (pinfunction "B_B") (pintype "passive"))
    )
    (net (code "66") (name "Net-(R24-Pad1)") (class "Default")
      (node (ref "R24") (pin "1") (pinfunction "1_1") (pintype "passive"))
      (node (ref "T15") (pin "C") (pinfunction "C_C") (pintype "passive"))
    )
    (net (code "67") (name "Net-(R25-Pad1)") (class "Default")
      (node (ref "R25") (pin "1") (pinfunction "1_1") (pintype "passive"))
      (node (ref "T15") (pin "B") (pinfunction "B_B") (pintype "passive"))
    )
    (net (code "68") (name "Net-(R26-Pad2)") (class "Default")
      (node (ref "R26") (pin "2") (pinfunction "2_2") (pintype "passive"))
      (node (ref "T18") (pin "C") (pinfunction "C_C") (pintype "passive"))
    )
    (net (code "69") (name "Net-(R27-Pad1)") (class "Default")
      (node (ref "R27") (pin "1") (pinfunction "1_1") (pintype "passive"))
      (node (ref "R28") (pin "2") (pinfunction "2_2") (pintype "passive"))
      (node (ref "T18") (pin "B") (pinfunction "B_B") (pintype "passive"))
    )
    (net (code "70") (name "Net-(R28-Pad1)") (class "Default")
      (node (ref "R28") (pin "1") (pinfunction "1_1") (pintype "passive"))
      (node (ref "T17") (pin "C") (pinfunction "C_C") (pintype "passive"))
    )
    (net (code "71") (name "Net-(R29-Pad1)") (class "Default")
      (node (ref "R29") (pin "1") (pinfunction "1_1") (pintype "passive"))
      (node (ref "T17") (pin "B") (pinfunction "B_B") (pintype "passive"))
    )
    (net (code "72") (name "Net-(R30-Pad2)") (class "Default")
      (node (ref "R30") (pin "2") (pinfunction "2_2") (pintype "passive"))
      (node (ref "T20") (pin "C") (pinfunction "C_C") (pintype "passive"))
    )
    (net (code "73") (name "Net-(R31-Pad1)") (class "Default")
      (node (ref "R31") (pin "1") (pinfunction "1_1") (pintype "passive"))
      (node (ref "R32") (pin "2") (pinfunction "2_2") (pintype "passive"))
      (node (ref "T20") (pin "B") (pinfunction "B_B") (pintype "passive"))
    )
    (net (code "74") (name "Net-(R32-Pad1)") (class "Default")
      (node (ref "R32") (pin "1") (pinfunction "1_1") (pintype "passive"))
      (node (ref "T19") (pin "C") (pinfunction "C_C") (pintype "passive"))
    )
    (net (code "75") (name "Net-(R33-Pad1)") (class "Default")
      (node (ref "R33") (pin "1") (pinfunction "1_1") (pintype "passive"))
      (node (ref "T19") (pin "B") (pinfunction "B_B") (pintype "passive"))
    )
    (net (code "76") (name "Net-(R34-Pad2)") (class "Default")
      (node (ref "R34") (pin "2") (pinfunction "2_2") (pintype "passive"))
      (node (ref "T22") (pin "C") (pinfunction "C_C") (pintype "passive"))
    )
    (net (code "77") (name "Net-(R35-Pad1)") (class "Default")
      (node (ref "R35") (pin "1") (pinfunction "1_1") (pintype "passive"))
      (node (ref "R36") (pin "2") (pinfunction "2_2") (pintype "passive"))
      (node (ref "T22") (pin "B") (pinfunction "B_B") (pintype "passive"))
    )
    (net (code "78") (name "Net-(R36-Pad1)") (class "Default")
      (node (ref "R36") (pin "1") (pinfunction "1_1") (pintype "passive"))
      (node (ref "T21") (pin "C") (pinfunction "C_C") (pintype "passive"))
    )
    (net (code "79") (name "Net-(R37-Pad1)") (class "Default")
      (node (ref "R37") (pin "1") (pinfunction "1_1") (pintype "passive"))
      (node (ref "T21") (pin "B") (pinfunction "B_B") (pintype "passive"))
    )
    (net (code "80") (name "Net-(R41-Pad2)") (class "Default")
      (node (ref "R41") (pin "2") (pinfunction "2_2") (pintype "passive"))
      (node (ref "T2") (pin "C") (pinfunction "C_C") (pintype "passive"))
    )
    (net (code "81") (name "Net-(S1-P)") (class "Default")
      (node (ref "JP1") (pin "2") (pinfunction "2_2") (pintype "passive"))
      (node (ref "S1") (pin "3") (pinfunction "P_3") (pintype "passive"))
      (node (ref "S1") (pin "4") (pinfunction "P1_4") (pintype "passive"))
      (node (ref "U1") (pin "3") (pinfunction "PIO0_12_3") (pintype "bidirectional"))
    )
    (net (code "82") (name "Net-(S2-P)") (class "Default")
      (node (ref "S2") (pin "3") (pinfunction "P_3") (pintype "passive"))
      (node (ref "S2") (pin "4") (pinfunction "P1_4") (pintype "passive"))
      (node (ref "SV1") (pin "15") (pinfunction "15_15") (pintype "passive"))
      (node (ref "U1") (pin "4") (pinfunction "~{RESET}/PIO0_5_4") (pintype "bidirectional"))
    )
    (net (code "83") (name "Net-(U1-PIO0_0{slash}ACMP_I1{slash}TDO)") (class "Default")
      (node (ref "JP3") (pin "3") (pinfunction "3_3") (pintype "passive"))
      (node (ref "U1") (pin "19") (pinfunction "PIO0_0/ACMP_I1/TDO_19") (pintype "bidirectional"))
    )
    (net (code "84") (name "Net-(U1-PIO0_6{slash}VDDCMP)") (class "Default")
      (node (ref "JP3") (pin "2") (pinfunction "2_2") (pintype "passive"))
      (node (ref "U1") (pin "18") (pinfunction "PIO0_6/VDDCMP_18") (pintype "bidirectional"))
    )
    (net (code "85") (name "Net-(U1-PIO0_8{slash}XTALIN)") (class "Default")
      (node (ref "C9") (pin "1") (pinfunction "1_1") (pintype "passive"))
      (node (ref "U1") (pin "14") (pinfunction "PIO0_8/XTALIN_14") (pintype "bidirectional"))
      (node (ref "X1") (pin "3") (pinfunction "PIN2_3") (pintype "bidirectional"))
    )
    (net (code "86") (name "Net-(U1-PIO0_9{slash}XTALOUT)") (class "Default")
      (node (ref "C8") (pin "1") (pinfunction "1_1") (pintype "passive"))
      (node (ref "U1") (pin "13") (pinfunction "PIO0_9/XTALOUT_13") (pintype "bidirectional"))
      (node (ref "X1") (pin "1") (pinfunction "PIN1_1") (pintype "bidirectional"))
    )
    (net (code "87") (name "Net-(U1-SWCLK{slash}PIO0_3{slash}TCK)") (class "Default")
      (node (ref "SV1") (pin "9") (pinfunction "9_9") (pintype "passive"))
      (node (ref "U1") (pin "6") (pinfunction "SWCLK/PIO0_3/TCK_6") (pintype "bidirectional"))
    )
    (net (code "88") (name "Net-(U1-SWDIO{slash}PIO0_2{slash}TMS)") (class "Default")
      (node (ref "SV1") (pin "7") (pinfunction "7_7") (pintype "passive"))
      (node (ref "U1") (pin "7") (pinfunction "SWDIO/PIO0_2/TMS_7") (pintype "bidirectional"))
    )
    (net (code "89") (name "S1") (class "Default")
      (node (ref "R33") (pin "2") (pinfunction "2_2") (pintype "passive"))
      (node (ref "U1") (pin "17") (pinfunction "PIO0_7_17") (pintype "bidirectional"))
    )
    (net (code "90") (name "S2") (class "Default")
      (node (ref "R37") (pin "2") (pinfunction "2_2") (pintype "passive"))
      (node (ref "U1") (pin "20") (pinfunction "PIO0_14_20") (pintype "bidirectional"))
    )
    (net (code "91") (name "V+") (class "Default")
      (node (ref "C12") (pin "+") (pinfunction "+_+") (pintype "passive"))
      (node (ref "D3") (pin "C") (pinfunction "C_C") (pintype "passive"))
      (node (ref "JP4") (pin "1") (pinfunction "1_1") (pintype "passive"))
      (node (ref "R1") (pin "2") (pinfunction "2_2") (pintype "passive"))
      (node (ref "R17") (pin "1") (pinfunction "1_1") (pintype "passive"))
      (node (ref "R19") (pin "2") (pinfunction "2_2") (pintype "passive"))
      (node (ref "R23") (pin "2") (pinfunction "2_2") (pintype "passive"))
      (node (ref "R27") (pin "2") (pinfunction "2_2") (pintype "passive"))
      (node (ref "R31") (pin "2") (pinfunction "2_2") (pintype "passive"))
      (node (ref "R35") (pin "2") (pinfunction "2_2") (pintype "passive"))
      (node (ref "T14") (pin "E") (pinfunction "E_E") (pintype "passive"))
      (node (ref "T16") (pin "E") (pinfunction "E_E") (pintype "passive"))
      (node (ref "T18") (pin "E") (pinfunction "E_E") (pintype "passive"))
      (node (ref "T2") (pin "E") (pinfunction "E_E") (pintype "passive"))
      (node (ref "T20") (pin "E") (pinfunction "E_E") (pintype "passive"))
      (node (ref "T22") (pin "E") (pinfunction "E_E") (pintype "passive"))
    )
    (net (code "92") (name "unconnected-(N1-DP-Pad10)") (class "Default")
      (node (ref "N1") (pin "10") (pinfunction "DP_10") (pintype "bidirectional"))
    )
    (net (code "93") (name "unconnected-(N1-IC-Pad4)") (class "Default")
      (node (ref "N1") (pin "4") (pinfunction "IC_4") (pintype "bidirectional"))
    )
    (net (code "94") (name "unconnected-(N2-DP-Pad10)") (class "Default")
      (node (ref "N2") (pin "10") (pinfunction "DP_10") (pintype "bidirectional"))
    )
    (net (code "95") (name "unconnected-(N2-IC-Pad4)") (class "Default")
      (node (ref "N2") (pin "4") (pinfunction "IC_4") (pintype "bidirectional"))
    )
    (net (code "96") (name "unconnected-(N3-DP-Pad10)") (class "Default")
      (node (ref "N3") (pin "10") (pinfunction "DP_10") (pintype "bidirectional"))
    )
    (net (code "97") (name "unconnected-(N3-IC-Pad4)") (class "Default")
      (node (ref "N3") (pin "4") (pinfunction "IC_4") (pintype "bidirectional"))
    )
    (net (code "98") (name "unconnected-(N4-DP-Pad10)") (class "Default")
      (node (ref "N4") (pin "10") (pinfunction "DP_10") (pintype "bidirectional"))
    )
    (net (code "99") (name "unconnected-(N4-IC-Pad4)") (class "Default")
      (node (ref "N4") (pin "4") (pinfunction "IC_4") (pintype "bidirectional"))
    )
    (net (code "100") (name "unconnected-(N5-DP-Pad10)") (class "Default")
      (node (ref "N5") (pin "10") (pinfunction "DP_10") (pintype "bidirectional"))
    )
    (net (code "101") (name "unconnected-(N5-IC-Pad4)") (class "Default")
      (node (ref "N5") (pin "4") (pinfunction "IC_4") (pintype "bidirectional"))
    )
    (net (code "102") (name "unconnected-(N6-DP-Pad10)") (class "Default")
      (node (ref "N6") (pin "10") (pinfunction "DP_10") (pintype "bidirectional"))
    )
    (net (code "103") (name "unconnected-(N6-IC-Pad4)") (class "Default")
      (node (ref "N6") (pin "4") (pinfunction "IC_4") (pintype "bidirectional"))
    )
    (net (code "104") (name "unconnected-(SV1-Pad2)") (class "Default")
      (node (ref "SV1") (pin "2") (pinfunction "2_2") (pintype "passive"))
    )
    (net (code "105") (name "unconnected-(SV1-Pad3)") (class "Default")
      (node (ref "SV1") (pin "3") (pinfunction "3_3") (pintype "passive"))
    )
    (net (code "106") (name "unconnected-(SV1-Pad5)") (class "Default")
      (node (ref "SV1") (pin "5") (pinfunction "5_5") (pintype "passive"))
    )
    (net (code "107") (name "unconnected-(SV1-Pad11)") (class "Default")
      (node (ref "SV1") (pin "11") (pinfunction "11_11") (pintype "passive"))
    )
    (net (code "108") (name "unconnected-(SV1-Pad13)") (class "Default")
      (node (ref "SV1") (pin "13") (pinfunction "13_13") (pintype "passive"))
    )
    (net (code "109") (name "unconnected-(SV1-Pad17)") (class "Default")
      (node (ref "SV1") (pin "17") (pinfunction "17_17") (pintype "passive"))
    )
    (net (code "110") (name "unconnected-(SV1-Pad19)") (class "Default")
      (node (ref "SV1") (pin "19") (pinfunction "19_19") (pintype "passive"))
    )
  )
)
